# MonthCalendar_VL53L0XBreakout_v0_1.net
KiCad netlist of a schematic drawn in EAGLE
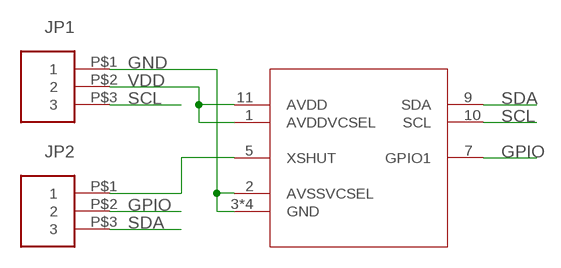
[diagram p0: schematic, sheet 1]

(export (version "E")
  (design (tool "Eeschema 10.0.6"))
  (components
    (comp (ref "JP1")
      (value "PINHEAD_1X350MIL")
      (footprint "eagle-import:PINHEAD_1X3_50MIL")
      (libsource (lib "eagle-import") (part "PINHEAD_1X350MIL"))
    )
    (comp (ref "JP2")
      (value "PINHEAD_1X350MIL")
      (footprint "eagle-import:PINHEAD_1X3_50MIL")
      (libsource (lib "eagle-import") (part "PINHEAD_1X350MIL"))
    )
    (comp (ref "U1")
      (value "VL53L0X")
      (footprint "eagle-import:VL53L0X")
      (libsource (lib "eagle-import") (part "VL53L0X"))
    )
  )
  (nets
    (net (code "1") (name "/GND") (class "Default")
      (node (ref "JP1") (pin "P$1") (pinfunction "1_P$1") (pintype "bidirectional"))
      (node (ref "U1") (pin "12") (pinfunction "GND_12") (pintype "power_in"))
      (node (ref "U1") (pin "2") (pinfunction "AVSSVCSEL_2") (pintype "power_in"))
      (node (ref "U1") (pin "3") (pinfunction "GND_3") (pintype "power_in"))
      (node (ref "U1") (pin "4") (pinfunction "GND_4") (pintype "power_in"))
      (node (ref "U1") (pin "6") (pinfunction "GND_6") (pintype "power_in"))
    )
    (net (code "2") (name "/GPIO") (class "Default")
      (node (ref "JP2") (pin "P$2") (pinfunction "2_P$2") (pintype "bidirectional"))
      (node (ref "U1") (pin "7") (pinfunction "GPIO1_7") (pintype "output"))
    )
    (net (code "3") (name "/SCL") (class "Default")
      (node (ref "JP1") (pin "P$3") (pinfunction "3_P$3") (pintype "bidirectional"))
      (node (ref "U1") (pin "10") (pinfunction "SCL_10") (pintype "bidirectional"))
    )
    (net (code "4") (name "/SDA") (class "Default")
      (node (ref "JP2") (pin "P$3") (pinfunction "3_P$3") (pintype "bidirectional"))
      (node (ref "U1") (pin "9") (pinfunction "SDA_9") (pintype "bidirectional"))
    )
    (net (code "5") (name "/VDD") (class "Default")
      (node (ref "JP1") (pin "P$2") (pinfunction "2_P$2") (pintype "bidirectional"))
      (node (ref "U1") (pin "1") (pinfunction "AVDDVCSEL_1") (pintype "power_in"))
      (node (ref "U1") (pin "11") (pinfunction "AVDD_11") (pintype "power_in"))
    )
    (net (code "6") (name "Net-(JP2-1)") (class "Default")
      (node (ref "JP2") (pin "P$1") (pinfunction "1_P$1") (pintype "bidirectional"))
      (node (ref "U1") (pin "5") (pinfunction "XSHUT_5") (pintype "input"))
    )
  )
)
